# CH340N4T-R0.net
KiCad netlist of a schematic drawn in Altium Designer
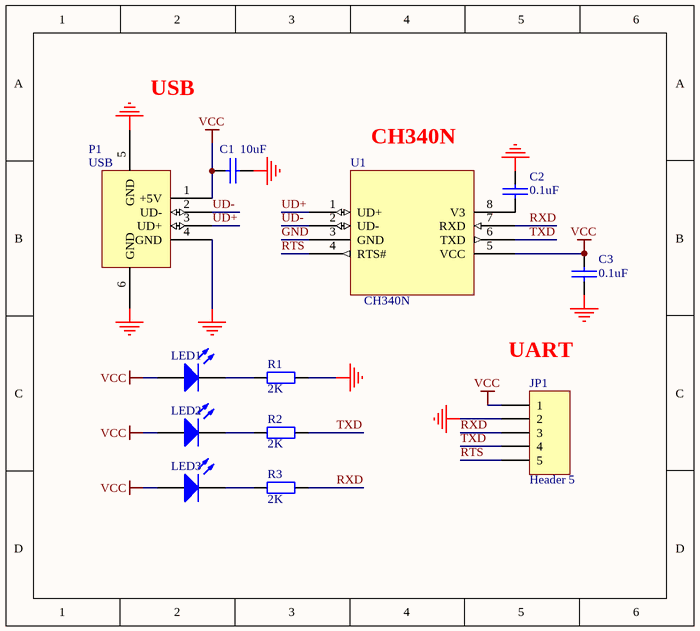
[diagram p0: CH340N4T-R0.SchDoc]

(export (version "E")
  (design (tool "Eeschema 10.0.6"))
  (components
    (comp (ref "C1")
      (value "10uF")
      (footprint "3216_C")
      (description "Capacitor")
      (libsource (lib "*") (part "CAP"))
    )
    (comp (ref "C2")
      (value "0.1uF")
      (footprint "0603_C")
      (description "Capacitor")
      (libsource (lib "*") (part "CAP"))
    )
    (comp (ref "C3")
      (value "0.1uF")
      (footprint "0603_C")
      (description "Capacitor")
      (libsource (lib "*") (part "CAP"))
    )
    (comp (ref "JP1")
      (value "Header 5")
      (footprint "SIP5-2.54mm")
      (description "Header, 5-Pin")
      (libsource (lib "*") (part "Header 5"))
    )
    (comp (ref "LED1")
      (value "PWR")
      (footprint "0603+")
      (description "Typical RED, GREEN, YELLOW, AMBER GaAs LED")
      (libsource (lib "*") (part "LED2"))
    )
    (comp (ref "LED2")
      (value "TXD")
      (footprint "0603+")
      (description "Typical RED, GREEN, YELLOW, AMBER GaAs LED")
      (libsource (lib "*") (part "LED2"))
    )
    (comp (ref "LED3")
      (value "RXD")
      (footprint "0603+")
      (description "Typical RED, GREEN, YELLOW, AMBER GaAs LED")
      (libsource (lib "*") (part "LED2"))
    )
    (comp (ref "P1") (value "USB") (footprint "USBAM") (libsource (lib "*") (part "USB")))
    (comp (ref "R1")
      (value "2K")
      (footprint "0603")
      (description "Resistor")
      (libsource (lib "*") (part "Res2"))
    )
    (comp (ref "R2")
      (value "2K")
      (footprint "0603")
      (description "Resistor")
      (libsource (lib "*") (part "Res2"))
    )
    (comp (ref "R3")
      (value "2K")
      (footprint "0603")
      (description "Resistor")
      (libsource (lib "*") (part "Res2"))
    )
    (comp (ref "U1")
      (value "CH340N")
      (footprint "SOP8")
      (description "USB to TTL Serial / UART")
      (libsource (lib "*") (part "CH340N"))
    )
  )
  (nets
    (net (code "1") (name "/RTS") (class "Default")
      (node (ref "JP1") (pin "5") (pinfunction "5_5") (pintype "passive"))
      (node (ref "U1") (pin "4") (pinfunction "RTS#_4") (pintype "output"))
    )
    (net (code "2") (name "/RXD") (class "Default")
      (node (ref "JP1") (pin "3") (pinfunction "3_3") (pintype "passive"))
      (node (ref "R3") (pin "2") (pinfunction "2_2") (pintype "passive"))
      (node (ref "U1") (pin "7") (pinfunction "RXD_7") (pintype "input"))
    )
    (net (code "3") (name "/TXD") (class "Default")
      (node (ref "JP1") (pin "4") (pinfunction "4_4") (pintype "passive"))
      (node (ref "R2") (pin "2") (pinfunction "2_2") (pintype "passive"))
      (node (ref "U1") (pin "6") (pinfunction "TXD_6") (pintype "output"))
    )
    (net (code "4") (name "/UD+") (class "Default")
      (node (ref "P1") (pin "3") (pinfunction "UD+_3") (pintype "bidirectional"))
      (node (ref "U1") (pin "1") (pinfunction "UD+_1") (pintype "bidirectional"))
    )
    (net (code "5") (name "/UD-") (class "Default")
      (node (ref "P1") (pin "2") (pinfunction "UD-_2") (pintype "bidirectional"))
      (node (ref "U1") (pin "2") (pinfunction "UD-_2") (pintype "bidirectional"))
    )
    (net (code "6") (name "GND") (class "Default")
      (node (ref "C1") (pin "2") (pinfunction "2_2") (pintype "passive"))
      (node (ref "C2") (pin "2") (pinfunction "2_2") (pintype "passive"))
      (node (ref "C3") (pin "1") (pinfunction "1_1") (pintype "passive"))
      (node (ref "JP1") (pin "2") (pinfunction "2_2") (pintype "passive"))
      (node (ref "P1") (pin "4") (pinfunction "GND_4") (pintype "power_in"))
      (node (ref "P1") (pin "5") (pinfunction "GND_5") (pintype "power_in"))
      (node (ref "P1") (pin "6") (pinfunction "GND_6") (pintype "power_in"))
      (node (ref "R1") (pin "2") (pinfunction "2_2") (pintype "passive"))
      (node (ref "U1") (pin "3") (pinfunction "GND_3") (pintype "power_in"))
    )
    (net (code "7") (name "Net-(LED1-K)") (class "Default")
      (node (ref "LED1") (pin "2") (pinfunction "K_2") (pintype "passive"))
      (node (ref "R1") (pin "1") (pinfunction "1_1") (pintype "passive"))
    )
    (net (code "8") (name "Net-(LED2-K)") (class "Default")
      (node (ref "LED2") (pin "2") (pinfunction "K_2") (pintype "passive"))
      (node (ref "R2") (pin "1") (pinfunction "1_1") (pintype "passive"))
    )
    (net (code "9") (name "Net-(LED3-K)") (class "Default")
      (node (ref "LED3") (pin "2") (pinfunction "K_2") (pintype "passive"))
      (node (ref "R3") (pin "1") (pinfunction "1_1") (pintype "passive"))
    )
    (net (code "10") (name "Net-(U1-V3)") (class "Default")
      (node (ref "C2") (pin "1") (pinfunction "1_1") (pintype "passive"))
      (node (ref "U1") (pin "8") (pinfunction "V3_8") (pintype "power_in"))
    )
    (net (code "11") (name "VCC") (class "Default")
      (node (ref "C1") (pin "1") (pinfunction "1_1") (pintype "passive"))
      (node (ref "C3") (pin "2") (pinfunction "2_2") (pintype "passive"))
      (node (ref "JP1") (pin "1") (pinfunction "1_1") (pintype "passive"))
      (node (ref "LED1") (pin "1") (pinfunction "A_1") (pintype "passive"))
      (node (ref "LED2") (pin "1") (pinfunction "A_1") (pintype "passive"))
      (node (ref "LED3") (pin "1") (pinfunction "A_1") (pintype "passive"))
      (node (ref "P1") (pin "1") (pinfunction "+5V_1") (pintype "power_in"))
      (node (ref "U1") (pin "5") (pinfunction "VCC_5") (pintype "power_in"))
    )
  )
)
